# Control_SCH.net
KiCad netlist of a schematic drawn in Altium Designer
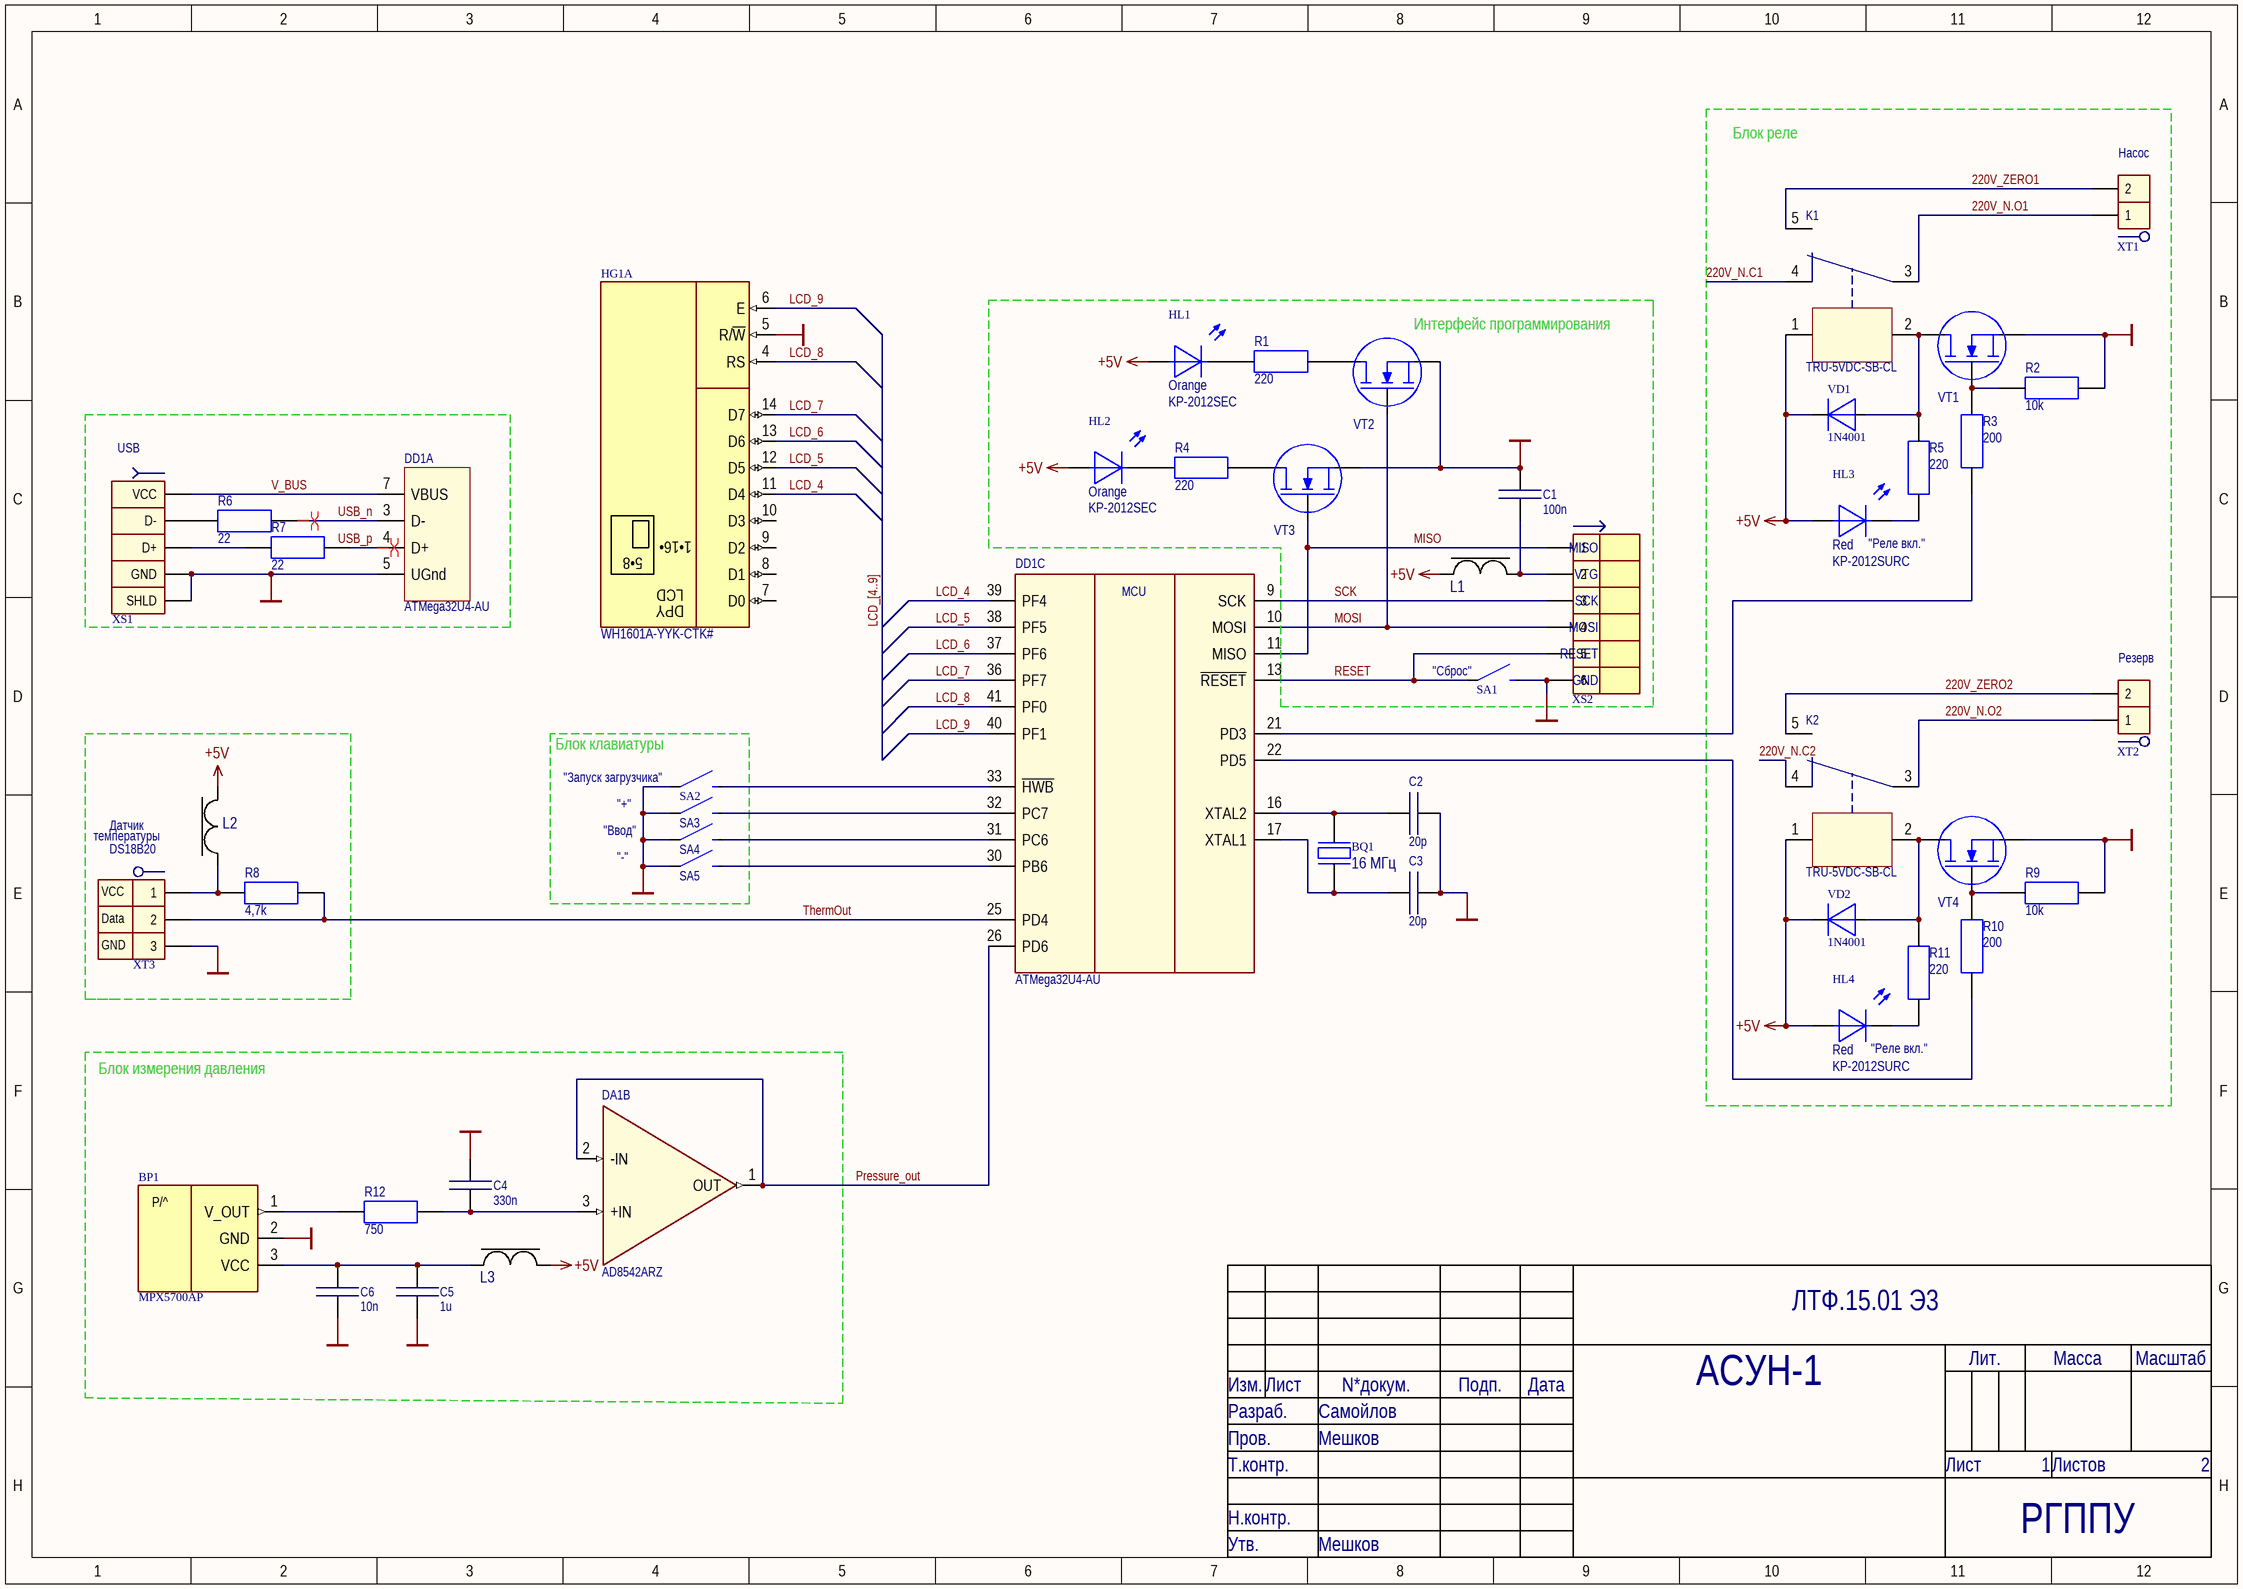
[diagram p0: Control_SCH.SchDoc]

(export (version "E")
  (design (tool "Eeschema 10.0.6"))
  (components
    (comp (ref "BP1")
      (value "MPX5700AP")
      (footprint "Sensor:MPX5700AP")
      (description "Pressure sensor, 700kPa")
      (fields (field (name "MANUFACTURER") "Freescale Semiconductor"))
      (libsource (lib "Sensor") (part "MPX5700AP"))
    )
    (comp (ref "BQ1")
      (value "16 МГц")
      (footprint "Piezoelectric:HC-49/S")
      (description "Piezoelectric elements")
      (fields
        (field (name "MANUFACTURER") "Taizhou")
        (field (name "MANUFACTURERPARTNUMBER") "16000 кГц 20ppm 20pF")
      )
      (libsource (lib "Piezoelectric") (part "Piezoelectric_16000"))
    )
    (comp (ref "C1")
      (value "100n")
      (footprint "SMDRC0805")
      (description "Generic capasitor non-polar")
      (fields (field (name "PARTNUMBER") "Capacitor 0805 100n"))
      (libsource (lib "library") (part "Capacitor"))
    )
    (comp (ref "C2")
      (value "20p")
      (footprint "SMDRC0805")
      (description "Generic capasitor non-polar")
      (fields (field (name "PARTNUMBER") "Capacitor 0805 20p"))
      (libsource (lib "library") (part "Capacitor"))
    )
    (comp (ref "C3")
      (value "20p")
      (footprint "SMDRC0805")
      (description "Generic capasitor non-polar")
      (fields (field (name "PARTNUMBER") "Capacitor 0805 20p"))
      (libsource (lib "library") (part "Capacitor"))
    )
    (comp (ref "C4")
      (value "330n")
      (footprint "SMDRC0805")
      (description "Generic capasitor non-polar")
      (fields (field (name "PARTNUMBER") "Capacitor 0805 330n"))
      (libsource (lib "library") (part "Capacitor"))
    )
    (comp (ref "C5")
      (value "1u")
      (footprint "SMDRC0805")
      (description "Generic capasitor non-polar")
      (fields (field (name "PARTNUMBER") "Capacitor 0805 1u"))
      (libsource (lib "library") (part "Capacitor"))
    )
    (comp (ref "C6")
      (value "10n")
      (footprint "SMDRC0805")
      (description "Generic capasitor non-polar")
      (fields (field (name "PARTNUMBER") "Capacitor 0805 10n"))
      (libsource (lib "library") (part "Capacitor"))
    )
    (comp (ref "DA1")
      (value "AD8542ARZ")
      (footprint "Op_amp:AD8542ARZ")
      (libsource (lib "Op_amp") (part "AD8542ARZ"))
    )
    (comp (ref "DD1")
      (value "ATMega32U4-AU")
      (footprint "Atmel Microcontroller 8-Bit Automotive AVR:44ML_L")
      (libsource (lib "") (part "ATMega32U4_1"))
    )
    (comp (ref "HG1")
      (value "WH1601A-YYK-CTK#")
      (footprint "Indicator:WH1601A")
      (description "Liquid crystal display")
      (fields
        (field (name "MANUFACTURER") "Winstar")
        (field (name "MANUFACTURERPARTNUMBER") "WH1601A-YYK-CTK#")
      )
      (libsource (lib "Indicator") (part "LCD 1601A"))
    )
    (comp (ref "HL1")
      (value "Orange")
      (footprint "Indicator:DIOMELF2012M")
      (description "Diod LED SMD Orange")
      (fields (field (name "MANUFACTURERPARTNUMBER") "KP-2012SEC"))
      (libsource (lib "Indicator") (part "LED1_O"))
    )
    (comp (ref "HL2")
      (value "Orange")
      (footprint "Indicator:DIOMELF2012M")
      (description "Diod LED SMD Orange")
      (fields (field (name "MANUFACTURERPARTNUMBER") "KP-2012SEC"))
      (libsource (lib "Indicator") (part "LED1_O"))
    )
    (comp (ref "HL3")
      (value "Red")
      (footprint "Indicator:DIOMELF2012M")
      (description "Diod LED SMD Red")
      (fields (field (name "MANUFACTURERPARTNUMBER") "KP-2012SURC"))
      (libsource (lib "Indicator") (part "LED1_R"))
    )
    (comp (ref "HL4")
      (value "Red")
      (footprint "Indicator:DIOMELF2012M")
      (description "Diod LED SMD Red")
      (fields (field (name "MANUFACTURERPARTNUMBER") "KP-2012SURC"))
      (libsource (lib "Indicator") (part "LED1_R"))
    )
    (comp (ref "K1")
      (value "TRU-5VDC-SB-CL")
      (footprint "Switch:TRU-5VDC-SB-CL")
      (libsource (lib "Switch") (part "TRU-5VDC-SB-CL"))
    )
    (comp (ref "K2")
      (value "TRU-5VDC-SB-CL")
      (footprint "Switch:TRU-5VDC-SB-CL")
      (libsource (lib "Switch") (part "TRU-5VDC-SB-CL"))
    )
    (comp (ref "L1")
      (value "MPZ1608S181A")
      (footprint "Inductor:INDC0603X03M")
      (description "Ferrite Bead")
      (libsource (lib "Inductor") (part "Ferrite Bead"))
    )
    (comp (ref "L2")
      (value "MPZ1608S181A")
      (footprint "Inductor:INDC0603X03M")
      (description "Ferrite Bead")
      (libsource (lib "") (part "Ferrite Bead_1"))
    )
    (comp (ref "L3")
      (value "MPZ1608S181A")
      (footprint "Inductor:INDC0603X03M")
      (description "Ferrite Bead")
      (libsource (lib "Inductor") (part "Ferrite Bead"))
    )
    (comp (ref "R1")
      (value "220")
      (footprint "SMDRC0805")
      (description "Generic resistor")
      (fields (field (name "PARTNUMBER") "Resistor 0805 220"))
      (libsource (lib "") (part "Resistor_3"))
    )
    (comp (ref "R2")
      (value "10k")
      (footprint "SMDRC0805")
      (description "Generic resistor")
      (fields (field (name "PARTNUMBER") "Resistor 0805 10k"))
      (libsource (lib "library") (part "Resistor"))
    )
    (comp (ref "R3")
      (value "200")
      (footprint "SMDRC0805")
      (description "Generic resistor")
      (fields (field (name "PARTNUMBER") "Resistor 0805 200"))
      (libsource (lib "") (part "Resistor_2"))
    )
    (comp (ref "R4")
      (value "220")
      (footprint "SMDRC0805")
      (description "Generic resistor")
      (fields (field (name "PARTNUMBER") "Resistor 0805 220"))
      (libsource (lib "") (part "Resistor_3"))
    )
    (comp (ref "R5")
      (value "220")
      (footprint "SMDRC0805")
      (description "Generic resistor")
      (fields (field (name "PARTNUMBER") "Resistor 0805 220"))
      (libsource (lib "") (part "Resistor_1"))
    )
    (comp (ref "R6")
      (value "22")
      (footprint "SMDRC0805")
      (description "Generic resistor")
      (fields (field (name "PARTNUMBER") "Resistor 0805 22"))
      (libsource (lib "") (part "Resistor_1"))
    )
    (comp (ref "R7")
      (value "22")
      (footprint "SMDRC0805")
      (description "Generic resistor")
      (fields (field (name "PARTNUMBER") "Resistor 0805 22"))
      (libsource (lib "") (part "Resistor_1"))
    )
    (comp (ref "R8")
      (value "4,7k")
      (footprint "SMDRC0805")
      (description "Generic resistor")
      (fields (field (name "PARTNUMBER") "Resistor 0805 4,7k"))
      (libsource (lib "library") (part "Resistor"))
    )
    (comp (ref "R9")
      (value "10k")
      (footprint "SMDRC0805")
      (description "Generic resistor")
      (fields (field (name "PARTNUMBER") "Resistor 0805 10k"))
      (libsource (lib "library") (part "Resistor"))
    )
    (comp (ref "R10")
      (value "200")
      (footprint "SMDRC0805")
      (description "Generic resistor")
      (fields (field (name "PARTNUMBER") "Resistor 0805 200"))
      (libsource (lib "") (part "Resistor_2"))
    )
    (comp (ref "R11")
      (value "220")
      (footprint "SMDRC0805")
      (description "Generic resistor")
      (fields (field (name "PARTNUMBER") "Resistor 0805 220"))
      (libsource (lib "") (part "Resistor_1"))
    )
    (comp (ref "R12")
      (value "750")
      (footprint "SMDRC0805")
      (description "Generic resistor")
      (fields (field (name "PARTNUMBER") "Resistor 0805 750"))
      (libsource (lib "library") (part "Resistor"))
    )
    (comp (ref "SA1")
      (value "DTSM20-4.3")
      (footprint "Switch:DTSM20")
      (description "Switch open")
      (fields (field (name "MANUFACTURER") "Diptronics"))
      (libsource (lib "Switch") (part "Switch1_DTSM20-4.3"))
    )
    (comp (ref "SA2")
      (value "DTSM20-4.3")
      (footprint "Switch:DTSM20")
      (description "Switch open")
      (fields (field (name "MANUFACTURER") "Diptronics"))
      (libsource (lib "Switch") (part "Switch1_DTSM20-4.3"))
    )
    (comp (ref "SA3")
      (value "SWT14-13")
      (footprint "Switch:SWT14")
      (libsource (lib "Switch") (part "SWT-14-13"))
    )
    (comp (ref "SA4")
      (value "SWT14-13")
      (footprint "Switch:SWT14")
      (libsource (lib "Switch") (part "SWT-14-13"))
    )
    (comp (ref "SA5")
      (value "SWT14-13")
      (footprint "Switch:SWT14")
      (libsource (lib "Switch") (part "SWT-14-13"))
    )
    (comp (ref "VD1")
      (value "1N4001")
      (footprint "DIod:PinDiode")
      (description "Rectifying diode")
      (fields (field (name "MANUFACTURERPARTNUMBER") "1N4001"))
      (libsource (lib "Diod") (part "1N4001"))
    )
    (comp (ref "VD2")
      (value "1N4001")
      (footprint "DIod:PinDiode")
      (description "Rectifying diode")
      (fields (field (name "MANUFACTURERPARTNUMBER") "1N4001"))
      (libsource (lib "Diod") (part "1N4001"))
    )
    (comp (ref "VT1")
      (value "2N7002")
      (footprint "Standard:SOT23 (TO-236AB)")
      (description "60V, 300mA N-channel Trench MOSFET")
      (libsource (lib "Transistor") (part "2N7002 n-MOSFET"))
    )
    (comp (ref "VT2")
      (value "2N7002")
      (footprint "Standard:SOT23 (TO-236AB)")
      (description "60V, 300mA N-channel Trench MOSFET")
      (libsource (lib "Transistor") (part "2N7002 n-MOSFET"))
    )
    (comp (ref "VT3")
      (value "2N7002")
      (footprint "Standard:SOT23 (TO-236AB)")
      (description "60V, 300mA N-channel Trench MOSFET")
      (libsource (lib "Transistor") (part "2N7002 n-MOSFET"))
    )
    (comp (ref "VT4")
      (value "2N7002")
      (footprint "Standard:SOT23 (TO-236AB)")
      (description "60V, 300mA N-channel Trench MOSFET")
      (libsource (lib "Transistor") (part "2N7002 n-MOSFET"))
    )
    (comp (ref "XS1")
      (value "USB B A-09 РОЗЕТКА НА ПЛАТУ")
      (footprint "Connector:USB2.0B_Vertical")
      (description "USB-B Vertical")
      (libsource (lib "Connector") (part "USB2.0-BR"))
    )
    (comp (ref "XS2")
      (value "IDC-06M")
      (footprint "Connector:IDC-06M")
      (description "SPI connector")
      (libsource (lib "Connector") (part "Con6_M IDC-06M_SPI"))
    )
    (comp (ref "XT1")
      (value "305-021-12")
      (footprint "305-021-12")
      (description "Demountable connection  2-pin")
      (fields (field (name "MANUFACTURER") "Degson Electronics Co., Ltd"))
      (libsource (lib "Connector") (part "Con2_D 305-021-12"))
    )
    (comp (ref "XT2")
      (value "305-021-12")
      (footprint "305-021-12")
      (description "Demountable connection  2-pin")
      (fields (field (name "MANUFACTURER") "Degson Electronics Co., Ltd"))
      (libsource (lib "Connector") (part "Con2_D 305-021-12"))
    )
    (comp (ref "XT3")
      (value "305-031-12")
      (footprint "Connector:305-031-12")
      (description "Demountable connection 3-pin")
      (fields (field (name "MANUFACTURER") "Degson Electronics Co., Ltd"))
      (libsource (lib "Connector") (part "Con3_D 305-031-12"))
    )
  )
  (nets
    (net (code "1") (name "+5V") (class "Default")
      (node (ref "HL1") (pin "1") (pinfunction "1_1") (pintype "passive"))
      (node (ref "HL2") (pin "1") (pinfunction "1_1") (pintype "passive"))
      (node (ref "HL3") (pin "1") (pinfunction "1_1") (pintype "passive"))
      (node (ref "HL4") (pin "1") (pinfunction "1_1") (pintype "passive"))
      (node (ref "K1") (pin "1") (pinfunction "1_1") (pintype "passive"))
      (node (ref "K2") (pin "1") (pinfunction "1_1") (pintype "passive"))
      (node (ref "L1") (pin "1") (pinfunction "1_1") (pintype "passive"))
      (node (ref "L2") (pin "2") (pinfunction "2_2") (pintype "passive"))
      (node (ref "L3") (pin "2") (pinfunction "2_2") (pintype "passive"))
      (node (ref "VD1") (pin "K") (pinfunction "K_K") (pintype "passive"))
      (node (ref "VD2") (pin "K") (pinfunction "K_K") (pintype "passive"))
    )
    (net (code "2") (name "/220V_N.C1") (class "Default")
      (node (ref "K1") (pin "4") (pinfunction "4_4") (pintype "passive"))
    )
    (net (code "3") (name "/220V_N.C2") (class "Default")
      (node (ref "K2") (pin "4") (pinfunction "4_4") (pintype "passive"))
    )
    (net (code "4") (name "/220V_N.O1") (class "Default")
      (node (ref "K1") (pin "3") (pinfunction "3_3") (pintype "passive"))
      (node (ref "XT1") (pin "1") (pinfunction "1_1") (pintype "passive"))
    )
    (net (code "5") (name "/220V_N.O2") (class "Default")
      (node (ref "K2") (pin "3") (pinfunction "3_3") (pintype "passive"))
      (node (ref "XT2") (pin "1") (pinfunction "1_1") (pintype "passive"))
    )
    (net (code "6") (name "/220V_ZERO1") (class "Default")
      (node (ref "K1") (pin "5") (pinfunction "5_5") (pintype "passive"))
      (node (ref "XT1") (pin "2") (pinfunction "2_2") (pintype "passive"))
    )
    (net (code "7") (name "/220V_ZERO2") (class "Default")
      (node (ref "K2") (pin "5") (pinfunction "5_5") (pintype "passive"))
      (node (ref "XT2") (pin "2") (pinfunction "2_2") (pintype "passive"))
    )
    (net (code "8") (name "/LCD_4") (class "Default")
      (node (ref "DD1") (pin "39") (pinfunction "PF4_39") (pintype "passive"))
      (node (ref "HG1") (pin "11") (pinfunction "D4_11") (pintype "bidirectional"))
    )
    (net (code "9") (name "/LCD_5") (class "Default")
      (node (ref "DD1") (pin "38") (pinfunction "PF5_38") (pintype "passive"))
      (node (ref "HG1") (pin "12") (pinfunction "D5_12") (pintype "bidirectional"))
    )
    (net (code "10") (name "/LCD_6") (class "Default")
      (node (ref "DD1") (pin "37") (pinfunction "PF6_37") (pintype "passive"))
      (node (ref "HG1") (pin "13") (pinfunction "D6_13") (pintype "bidirectional"))
    )
    (net (code "11") (name "/LCD_7") (class "Default")
      (node (ref "DD1") (pin "36") (pinfunction "PF7_36") (pintype "passive"))
      (node (ref "HG1") (pin "14") (pinfunction "D7_14") (pintype "bidirectional"))
    )
    (net (code "12") (name "/LCD_8") (class "Default")
      (node (ref "DD1") (pin "41") (pinfunction "PF0_41") (pintype "passive"))
      (node (ref "HG1") (pin "4") (pinfunction "RS_4") (pintype "input"))
    )
    (net (code "13") (name "/LCD_9") (class "Default")
      (node (ref "DD1") (pin "40") (pinfunction "PF1_40") (pintype "passive"))
      (node (ref "HG1") (pin "6") (pinfunction "E_6") (pintype "input"))
    )
    (net (code "15") (name "/MISO") (class "Default")
      (node (ref "DD1") (pin "11") (pinfunction "MISO_11") (pintype "passive"))
      (node (ref "VT3") (pin "1") (pinfunction "G_1") (pintype "passive"))
      (node (ref "XS2") (pin "1") (pinfunction "1_1") (pintype "passive"))
    )
    (net (code "16") (name "/MOSI") (class "Default")
      (node (ref "DD1") (pin "10") (pinfunction "MOSI_10") (pintype "passive"))
      (node (ref "VT2") (pin "1") (pinfunction "G_1") (pintype "passive"))
      (node (ref "XS2") (pin "4") (pinfunction "4_4") (pintype "passive"))
    )
    (net (code "17") (name "/Pressure_out") (class "Default")
      (node (ref "DA1") (pin "1") (pinfunction "OUT_1") (pintype "output"))
      (node (ref "DA1") (pin "2") (pinfunction "-IN_2") (pintype "input"))
      (node (ref "DD1") (pin "26") (pinfunction "PD6_26") (pintype "passive"))
    )
    (net (code "18") (name "/RESET") (class "Default")
      (node (ref "DD1") (pin "13") (pinfunction "~{RESET}_13") (pintype "passive"))
      (node (ref "SA1") (pin "1") (pinfunction "1_1") (pintype "passive"))
      (node (ref "XS2") (pin "5") (pinfunction "5_5") (pintype "passive"))
    )
    (net (code "19") (name "/SCK") (class "Default")
      (node (ref "DD1") (pin "9") (pinfunction "SCK_9") (pintype "passive"))
      (node (ref "XS2") (pin "3") (pinfunction "3_3") (pintype "passive"))
    )
    (net (code "20") (name "/ThermOut") (class "Default")
      (node (ref "DD1") (pin "25") (pinfunction "PD4_25") (pintype "passive"))
      (node (ref "R8") (pin "2") (pinfunction "2_2") (pintype "passive"))
      (node (ref "XT3") (pin "2") (pinfunction "2_2") (pintype "passive"))
    )
    (net (code "21") (name "/USB_n") (class "Default")
      (node (ref "DD1") (pin "3") (pinfunction "D-_3") (pintype "passive"))
      (node (ref "R6") (pin "1") (pinfunction "1_1") (pintype "passive"))
    )
    (net (code "23") (name "/V_BUS") (class "Default")
      (node (ref "DD1") (pin "7") (pinfunction "VBUS_7") (pintype "passive"))
      (node (ref "XS1") (pin "VCC") (pinfunction "VCC_VCC") (pintype "passive"))
    )
    (net (code "24") (name "GND") (class "Default")
      (node (ref "BP1") (pin "2") (pinfunction "GND_2") (pintype "power_in"))
      (node (ref "C1") (pin "2") (pintype "passive"))
      (node (ref "C2") (pin "2") (pintype "passive"))
      (node (ref "C3") (pin "2") (pintype "passive"))
      (node (ref "C4") (pin "2") (pintype "passive"))
      (node (ref "C5") (pin "1") (pintype "passive"))
      (node (ref "C6") (pin "1") (pintype "passive"))
      (node (ref "DD1") (pin "5") (pinfunction "UGnd_5") (pintype "passive"))
      (node (ref "HG1") (pin "5") (pinfunction "R/~{W}_5") (pintype "input"))
      (node (ref "R2") (pin "2") (pinfunction "2_2") (pintype "passive"))
      (node (ref "R9") (pin "2") (pinfunction "2_2") (pintype "passive"))
      (node (ref "SA1") (pin "2") (pinfunction "2_2") (pintype "passive"))
      (node (ref "SA2") (pin "1") (pinfunction "1_1") (pintype "passive"))
      (node (ref "SA3") (pin "1") (pinfunction "1_1") (pintype "passive"))
      (node (ref "SA4") (pin "1") (pinfunction "1_1") (pintype "passive"))
      (node (ref "SA5") (pin "1") (pinfunction "1_1") (pintype "passive"))
      (node (ref "VT1") (pin "2") (pinfunction "S_2") (pintype "passive"))
      (node (ref "VT2") (pin "2") (pinfunction "S_2") (pintype "passive"))
      (node (ref "VT3") (pin "2") (pinfunction "S_2") (pintype "passive"))
      (node (ref "VT4") (pin "2") (pinfunction "S_2") (pintype "passive"))
      (node (ref "XS1") (pin "GND") (pinfunction "GND_GND") (pintype "passive"))
      (node (ref "XS1") (pin "SHLD") (pinfunction "SHLD_SHLD") (pintype "passive"))
      (node (ref "XS2") (pin "6") (pinfunction "6_6") (pintype "passive"))
      (node (ref "XT3") (pin "3") (pinfunction "3_3") (pintype "passive"))
    )
    (net (code "25") (name "Net-(BP1-VCC)") (class "Default")
      (node (ref "BP1") (pin "3") (pinfunction "VCC_3") (pintype "power_in"))
      (node (ref "C5") (pin "2") (pintype "passive"))
      (node (ref "C6") (pin "2") (pintype "passive"))
      (node (ref "L3") (pin "1") (pinfunction "1_1") (pintype "passive"))
    )
    (net (code "26") (name "Net-(BP1-V_OUT)") (class "Default")
      (node (ref "BP1") (pin "1") (pinfunction "V_OUT_1") (pintype "output"))
      (node (ref "R12") (pin "1") (pinfunction "1_1") (pintype "passive"))
    )
    (net (code "27") (name "Net-(C1-Pad1)") (class "Default")
      (node (ref "C1") (pin "1") (pintype "passive"))
      (node (ref "L1") (pin "2") (pinfunction "2_2") (pintype "passive"))
      (node (ref "XS2") (pin "2") (pinfunction "2_2") (pintype "passive"))
    )
    (net (code "28") (name "Net-(DA1B-+IN)") (class "Default")
      (node (ref "C4") (pin "1") (pintype "passive"))
      (node (ref "DA1") (pin "3") (pinfunction "+IN_3") (pintype "input"))
      (node (ref "R12") (pin "2") (pinfunction "2_2") (pintype "passive"))
    )
    (net (code "29") (name "Net-(DD1A-D+)") (class "Default")
      (node (ref "DD1") (pin "4") (pinfunction "D+_4") (pintype "passive"))
      (node (ref "R7") (pin "1") (pinfunction "1_1") (pintype "passive"))
    )
    (net (code "30") (name "Net-(DD1C-PB6)") (class "Default")
      (node (ref "DD1") (pin "30") (pinfunction "PB6_30") (pintype "passive"))
      (node (ref "SA5") (pin "2") (pinfunction "2_2") (pintype "passive"))
    )
    (net (code "31") (name "Net-(DD1C-PC6)") (class "Default")
      (node (ref "DD1") (pin "31") (pinfunction "PC6_31") (pintype "passive"))
      (node (ref "SA4") (pin "2") (pinfunction "2_2") (pintype "passive"))
    )
    (net (code "32") (name "Net-(DD1C-PC7)") (class "Default")
      (node (ref "DD1") (pin "32") (pinfunction "PC7_32") (pintype "passive"))
      (node (ref "SA3") (pin "2") (pinfunction "2_2") (pintype "passive"))
    )
    (net (code "33") (name "Net-(DD1C-PD3)") (class "Default")
      (node (ref "DD1") (pin "21") (pinfunction "PD3_21") (pintype "passive"))
      (node (ref "R3") (pin "1") (pinfunction "1_1") (pintype "passive"))
    )
    (net (code "34") (name "Net-(DD1C-PD5)") (class "Default")
      (node (ref "DD1") (pin "22") (pinfunction "PD5_22") (pintype "passive"))
      (node (ref "R10") (pin "1") (pinfunction "1_1") (pintype "passive"))
    )
    (net (code "35") (name "Net-(DD1C-XTAL1)") (class "Default")
      (node (ref "BQ1") (pin "1") (pinfunction "1_1") (pintype "passive"))
      (node (ref "C3") (pin "1") (pintype "passive"))
      (node (ref "DD1") (pin "17") (pinfunction "XTAL1_17") (pintype "passive"))
    )
    (net (code "36") (name "Net-(DD1C-XTAL2)") (class "Default")
      (node (ref "BQ1") (pin "2") (pinfunction "2_2") (pintype "passive"))
      (node (ref "C2") (pin "1") (pintype "passive"))
      (node (ref "DD1") (pin "16") (pinfunction "XTAL2_16") (pintype "passive"))
    )
    (net (code "37") (name "Net-(DD1C-~{HWB})") (class "Default")
      (node (ref "DD1") (pin "33") (pinfunction "~{HWB}_33") (pintype "passive"))
      (node (ref "SA2") (pin "2") (pinfunction "2_2") (pintype "passive"))
    )
    (net (code "38") (name "Net-(HL1-Pad2)") (class "Default")
      (node (ref "HL1") (pin "2") (pinfunction "2_2") (pintype "passive"))
      (node (ref "R1") (pin "2") (pinfunction "2_2") (pintype "passive"))
    )
    (net (code "39") (name "Net-(HL2-Pad2)") (class "Default")
      (node (ref "HL2") (pin "2") (pinfunction "2_2") (pintype "passive"))
      (node (ref "R4") (pin "2") (pinfunction "2_2") (pintype "passive"))
    )
    (net (code "40") (name "Net-(HL3-Pad2)") (class "Default")
      (node (ref "HL3") (pin "2") (pinfunction "2_2") (pintype "passive"))
      (node (ref "R5") (pin "2") (pinfunction "2_2") (pintype "passive"))
    )
    (net (code "41") (name "Net-(HL4-Pad2)") (class "Default")
      (node (ref "HL4") (pin "2") (pinfunction "2_2") (pintype "passive"))
      (node (ref "R11") (pin "2") (pinfunction "2_2") (pintype "passive"))
    )
    (net (code "42") (name "Net-(L2-Pad1)") (class "Default")
      (node (ref "L2") (pin "1") (pinfunction "1_1") (pintype "passive"))
      (node (ref "R8") (pin "1") (pinfunction "1_1") (pintype "passive"))
      (node (ref "XT3") (pin "1") (pinfunction "1_1") (pintype "passive"))
    )
    (net (code "43") (name "Net-(R6-Pad2)") (class "Default")
      (node (ref "R6") (pin "2") (pinfunction "2_2") (pintype "passive"))
      (node (ref "XS1") (pin "D-") (pinfunction "D-_D-") (pintype "passive"))
    )
    (net (code "44") (name "Net-(R7-Pad2)") (class "Default")
      (node (ref "R7") (pin "2") (pinfunction "2_2") (pintype "passive"))
      (node (ref "XS1") (pin "D+") (pinfunction "D+_D+") (pintype "passive"))
    )
    (net (code "45") (name "Net-(VT1-D)") (class "Default")
      (node (ref "K1") (pin "2") (pinfunction "2_2") (pintype "passive"))
      (node (ref "R5") (pin "1") (pinfunction "1_1") (pintype "passive"))
      (node (ref "VD1") (pin "A") (pinfunction "A_A") (pintype "passive"))
      (node (ref "VT1") (pin "3") (pinfunction "D_3") (pintype "passive"))
    )
    (net (code "46") (name "Net-(VT1-G)") (class "Default")
      (node (ref "R2") (pin "1") (pinfunction "1_1") (pintype "passive"))
      (node (ref "R3") (pin "2") (pinfunction "2_2") (pintype "passive"))
      (node (ref "VT1") (pin "1") (pinfunction "G_1") (pintype "passive"))
    )
    (net (code "47") (name "Net-(VT2-D)") (class "Default")
      (node (ref "R1") (pin "1") (pinfunction "1_1") (pintype "passive"))
      (node (ref "VT2") (pin "3") (pinfunction "D_3") (pintype "passive"))
    )
    (net (code "48") (name "Net-(VT3-D)") (class "Default")
      (node (ref "R4") (pin "1") (pinfunction "1_1") (pintype "passive"))
      (node (ref "VT3") (pin "3") (pinfunction "D_3") (pintype "passive"))
    )
    (net (code "49") (name "Net-(VT4-D)") (class "Default")
      (node (ref "K2") (pin "2") (pinfunction "2_2") (pintype "passive"))
      (node (ref "R11") (pin "1") (pinfunction "1_1") (pintype "passive"))
      (node (ref "VD2") (pin "A") (pinfunction "A_A") (pintype "passive"))
      (node (ref "VT4") (pin "3") (pinfunction "D_3") (pintype "passive"))
    )
    (net (code "50") (name "Net-(VT4-G)") (class "Default")
      (node (ref "R10") (pin "2") (pinfunction "2_2") (pintype "passive"))
      (node (ref "R9") (pin "1") (pinfunction "1_1") (pintype "passive"))
      (node (ref "VT4") (pin "1") (pinfunction "G_1") (pintype "passive"))
    )
    (net (code "51") (name "unconnected-(HG1A-D0-Pad7)") (class "Default")
      (node (ref "HG1") (pin "7") (pinfunction "D0_7") (pintype "bidirectional"))
    )
    (net (code "52") (name "unconnected-(HG1A-D1-Pad8)") (class "Default")
      (node (ref "HG1") (pin "8") (pinfunction "D1_8") (pintype "bidirectional"))
    )
    (net (code "53") (name "unconnected-(HG1A-D2-Pad9)") (class "Default")
      (node (ref "HG1") (pin "9") (pinfunction "D2_9") (pintype "bidirectional"))
    )
    (net (code "54") (name "unconnected-(HG1A-D3-Pad10)") (class "Default")
      (node (ref "HG1") (pin "10") (pinfunction "D3_10") (pintype "bidirectional"))
    )
  )
)
